# SynchrBuckConverter.net
KiCad netlist of a schematic drawn in Altium Designer
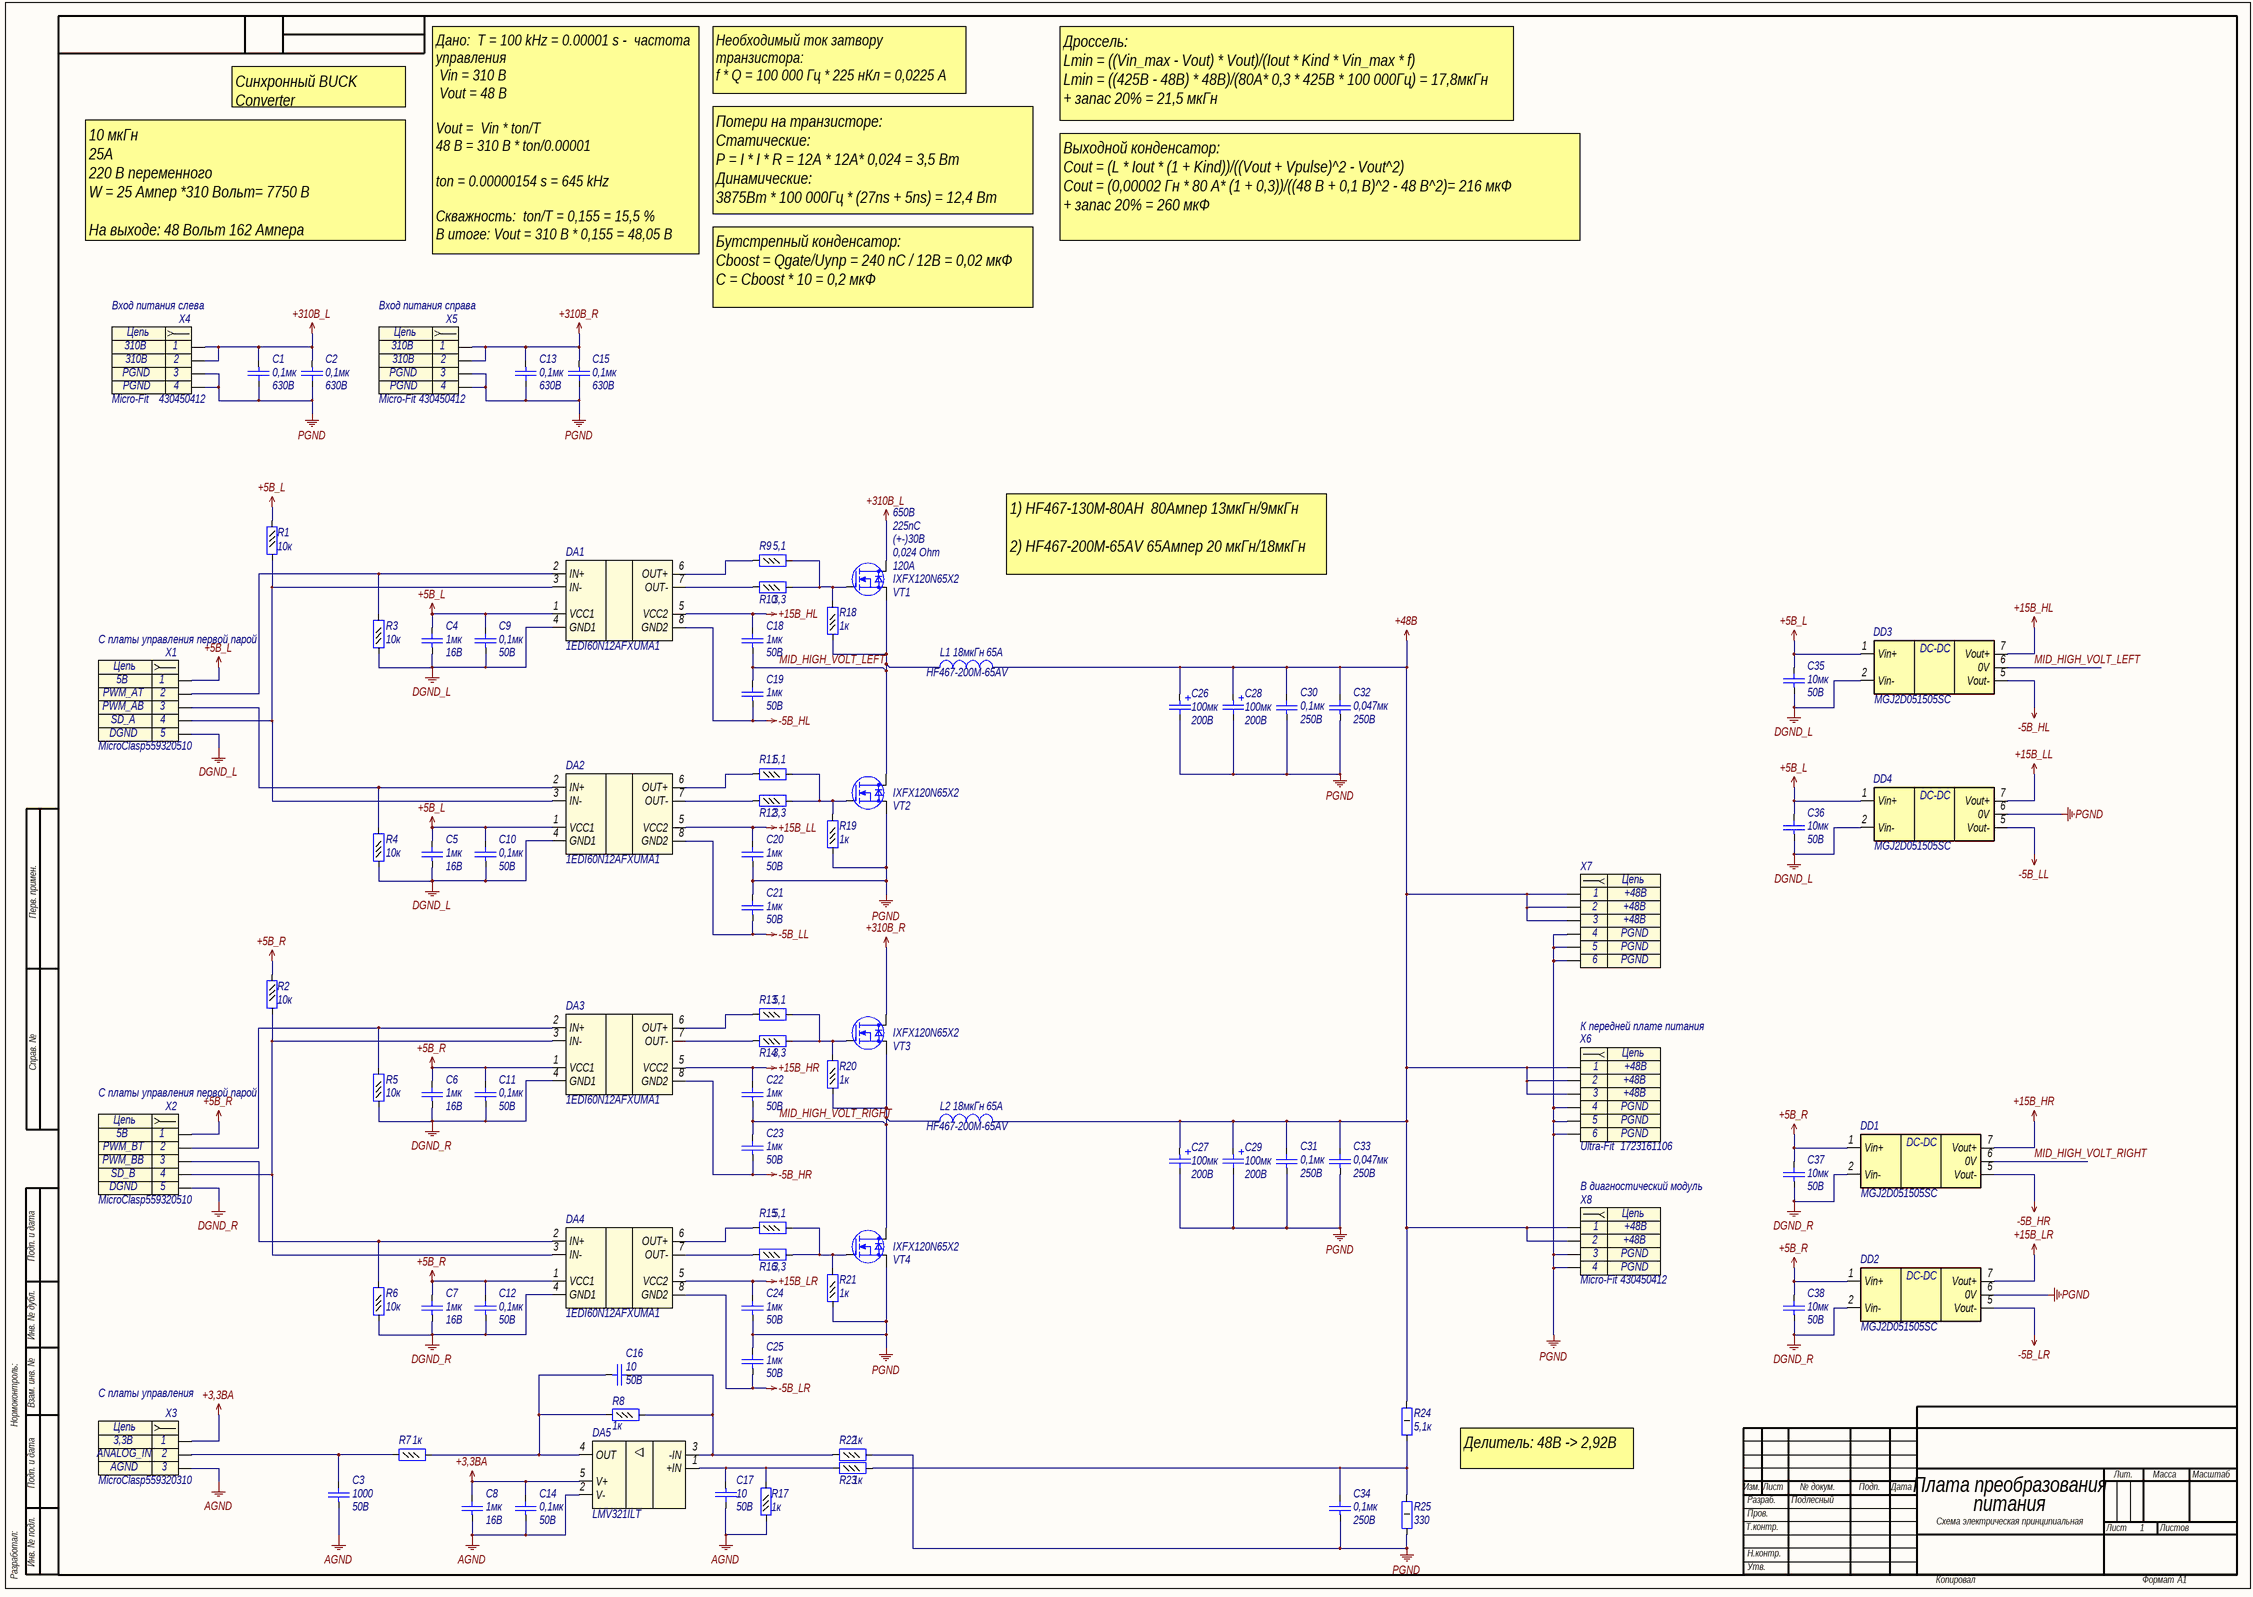
[diagram p0: SynchrBuckConverter.SchDoc]

(export (version "E")
  (design (tool "Eeschema 10.0.6"))
  (components
    (comp (ref "C1")
      (value "0,1мк")
      (footprint "C1812")
      (description "Конденсатор")
      (fields (field (name "VOLTAGE") "630В") (field (name "PART NUMBER") "GRM43DR72J104KW01L"))
      (libsource (lib "MOP44") (part "Capacitor"))
    )
    (comp (ref "C2")
      (value "0,1мк")
      (footprint "C1812")
      (description "Конденсатор")
      (fields (field (name "VOLTAGE") "630В") (field (name "PART NUMBER") "GRM43DR72J104KW01L"))
      (libsource (lib "MOP44") (part "Capacitor"))
    )
    (comp (ref "C3")
      (value "1000")
      (footprint "C0402")
      (description "Конденсатор")
      (fields
        (field (name "VOLTAGE") "50B")
        (field (name "PART NUMBER") "GRM1555C1H102J")
        (field (name "Comment") "Capacitor")
      )
      (libsource (lib "MOP44") (part "Capacitor"))
    )
    (comp (ref "C4")
      (value "1мк")
      (footprint "C0603")
      (description "Конденсатор")
      (fields (field (name "VOLTAGE") "16B") (field (name "PART NUMBER") "GRM188R71C105KA12D**"))
      (libsource (lib "MOP44") (part "Capacitor"))
    )
    (comp (ref "C5")
      (value "1мк")
      (footprint "C0603")
      (description "Конденсатор")
      (fields (field (name "VOLTAGE") "16B") (field (name "PART NUMBER") "GRM188R71C105KA12D**"))
      (libsource (lib "MOP44") (part "Capacitor"))
    )
    (comp (ref "C6")
      (value "1мк")
      (footprint "C0603")
      (description "Конденсатор")
      (fields (field (name "VOLTAGE") "16B") (field (name "PART NUMBER") "GRM188R71C105KA12D**"))
      (libsource (lib "MOP44") (part "Capacitor"))
    )
    (comp (ref "C7")
      (value "1мк")
      (footprint "C0603")
      (description "Конденсатор")
      (fields (field (name "VOLTAGE") "16B") (field (name "PART NUMBER") "GRM188R71C105KA12D**"))
      (libsource (lib "MOP44") (part "Capacitor"))
    )
    (comp (ref "C8")
      (value "1мк")
      (footprint "C0603")
      (description "Конденсатор")
      (fields (field (name "VOLTAGE") "16B") (field (name "PART NUMBER") "GRM188R71C105KA12D**"))
      (libsource (lib "MOP44") (part "Capacitor"))
    )
    (comp (ref "C9")
      (value "0,1мк")
      (footprint "C0402")
      (description "Конденсатор")
      (fields (field (name "VOLTAGE") "50В") (field (name "PART NUMBER") "GRM155R71H104KE14D"))
      (libsource (lib "MOP44") (part "Capacitor"))
    )
    (comp (ref "C10")
      (value "0,1мк")
      (footprint "C0402")
      (description "Конденсатор")
      (fields (field (name "VOLTAGE") "50В") (field (name "PART NUMBER") "GRM155R71H104KE14D"))
      (libsource (lib "MOP44") (part "Capacitor"))
    )
    (comp (ref "C11")
      (value "0,1мк")
      (footprint "C0402")
      (description "Конденсатор")
      (fields (field (name "VOLTAGE") "50В") (field (name "PART NUMBER") "GRM155R71H104KE14D"))
      (libsource (lib "MOP44") (part "Capacitor"))
    )
    (comp (ref "C12")
      (value "0,1мк")
      (footprint "C0402")
      (description "Конденсатор")
      (fields (field (name "VOLTAGE") "50В") (field (name "PART NUMBER") "GRM155R71H104KE14D"))
      (libsource (lib "MOP44") (part "Capacitor"))
    )
    (comp (ref "C13")
      (value "0,1мк")
      (footprint "C1812")
      (description "Конденсатор")
      (fields (field (name "VOLTAGE") "630В") (field (name "PART NUMBER") "GRM43DR72J104KW01L"))
      (libsource (lib "MOP44") (part "Capacitor"))
    )
    (comp (ref "C14")
      (value "0,1мк")
      (footprint "C0402")
      (description "Конденсатор")
      (fields
        (field (name "VOLTAGE") "50В")
        (field (name "PART NUMBER") "GRM155R71H104KE14D")
        (field (name "Comment") "Capacitor")
      )
      (libsource (lib "MOP44") (part "Capacitor"))
    )
    (comp (ref "C15")
      (value "0,1мк")
      (footprint "C1812")
      (description "Конденсатор")
      (fields (field (name "VOLTAGE") "630В") (field (name "PART NUMBER") "GRM43DR72J104KW01L"))
      (libsource (lib "MOP44") (part "Capacitor"))
    )
    (comp (ref "C16")
      (value "10")
      (footprint "C0402")
      (description "Конденсатор")
      (fields
        (field (name "VOLTAGE") "50B")
        (field (name "PART NUMBER") "GRM1535C1H100J")
        (field (name "Comment") "Capacitor")
      )
      (libsource (lib "MOP44") (part "Capacitor"))
    )
    (comp (ref "C17")
      (value "10")
      (footprint "C0402")
      (description "Конденсатор")
      (fields
        (field (name "VOLTAGE") "50B")
        (field (name "PART NUMBER") "GRM1535C1H100J")
        (field (name "Comment") "Capacitor")
      )
      (libsource (lib "MOP44") (part "Capacitor"))
    )
    (comp (ref "C18")
      (value "1мк")
      (footprint "C0805")
      (description "Конденсатор")
      (fields (field (name "VOLTAGE") "50B") (field (name "PART NUMBER") "GRM21BR71H105K"))
      (libsource (lib "MOP44") (part "Capacitor"))
    )
    (comp (ref "C19")
      (value "1мк")
      (footprint "C0805")
      (description "Конденсатор")
      (fields (field (name "VOLTAGE") "50B") (field (name "PART NUMBER") "GRM21BR71H105K"))
      (libsource (lib "MOP44") (part "Capacitor"))
    )
    (comp (ref "C20")
      (value "1мк")
      (footprint "C0805")
      (description "Конденсатор")
      (fields (field (name "VOLTAGE") "50B") (field (name "PART NUMBER") "GRM21BR71H105K"))
      (libsource (lib "MOP44") (part "Capacitor"))
    )
    (comp (ref "C21")
      (value "1мк")
      (footprint "C0805")
      (description "Конденсатор")
      (fields (field (name "VOLTAGE") "50B") (field (name "PART NUMBER") "GRM21BR71H105K"))
      (libsource (lib "MOP44") (part "Capacitor"))
    )
    (comp (ref "C22")
      (value "1мк")
      (footprint "C0805")
      (description "Конденсатор")
      (fields (field (name "VOLTAGE") "50B") (field (name "PART NUMBER") "GRM21BR71H105K"))
      (libsource (lib "MOP44") (part "Capacitor"))
    )
    (comp (ref "C23")
      (value "1мк")
      (footprint "C0805")
      (description "Конденсатор")
      (fields (field (name "VOLTAGE") "50B") (field (name "PART NUMBER") "GRM21BR71H105K"))
      (libsource (lib "MOP44") (part "Capacitor"))
    )
    (comp (ref "C24")
      (value "1мк")
      (footprint "C0805")
      (description "Конденсатор")
      (fields (field (name "VOLTAGE") "50B") (field (name "PART NUMBER") "GRM21BR71H105K"))
      (libsource (lib "MOP44") (part "Capacitor"))
    )
    (comp (ref "C25")
      (value "1мк")
      (footprint "C0805")
      (description "Конденсатор")
      (fields (field (name "VOLTAGE") "50B") (field (name "PART NUMBER") "GRM21BR71H105K"))
      (libsource (lib "MOP44") (part "Capacitor"))
    )
    (comp (ref "C26")
      (value "100мк")
      (footprint "Cap_SMD_radial_polar(18x21.5)")
      (description "Конденсатор полярный")
      (fields
        (field (name "VOLTAGE") "200В")
        (field (name "PART NUMBER") "EEV-EB2D101M")
        (field (name "Comment") "Capacitor_pol")
      )
      (libsource (lib "MOP44") (part "Capacitor_pol"))
    )
    (comp (ref "C27")
      (value "100мк")
      (footprint "Cap_SMD_radial_polar(18x21.5)")
      (description "Конденсатор полярный")
      (fields
        (field (name "VOLTAGE") "200В")
        (field (name "PART NUMBER") "EEV-EB2D101M")
        (field (name "Comment") "Capacitor_pol")
      )
      (libsource (lib "MOP44") (part "Capacitor_pol"))
    )
    (comp (ref "C28")
      (value "100мк")
      (footprint "Cap_SMD_radial_polar(18x21.5)")
      (description "Конденсатор полярный")
      (fields
        (field (name "VOLTAGE") "200В")
        (field (name "PART NUMBER") "EEV-EB2D101M")
        (field (name "Comment") "Capacitor_pol")
      )
      (libsource (lib "MOP44") (part "Capacitor_pol"))
    )
    (comp (ref "C29")
      (value "100мк")
      (footprint "Cap_SMD_radial_polar(18x21.5)")
      (description "Конденсатор полярный")
      (fields
        (field (name "VOLTAGE") "200В")
        (field (name "PART NUMBER") "EEV-EB2D101M")
        (field (name "Comment") "Capacitor_pol")
      )
      (libsource (lib "MOP44") (part "Capacitor_pol"))
    )
    (comp (ref "C30")
      (value "0,1мк")
      (footprint "C1206")
      (description "Конденсатор")
      (fields (field (name "VOLTAGE") "250В") (field (name "PART NUMBER") "GRM31CR72E104K"))
      (libsource (lib "MOP44") (part "Capacitor"))
    )
    (comp (ref "C31")
      (value "0,1мк")
      (footprint "C1206")
      (description "Конденсатор")
      (fields (field (name "VOLTAGE") "250В") (field (name "PART NUMBER") "GRM31CR72E104K"))
      (libsource (lib "MOP44") (part "Capacitor"))
    )
    (comp (ref "C32")
      (value "0,047мк")
      (footprint "C1206")
      (description "Конденсатор")
      (fields (field (name "VOLTAGE") "250В") (field (name "PART NUMBER") "GRM31CR72E473K"))
      (libsource (lib "MOP44") (part "Capacitor"))
    )
    (comp (ref "C33")
      (value "0,047мк")
      (footprint "C1206")
      (description "Конденсатор")
      (fields (field (name "VOLTAGE") "250В") (field (name "PART NUMBER") "GRM31CR72E473K"))
      (libsource (lib "MOP44") (part "Capacitor"))
    )
    (comp (ref "C34")
      (value "0,1мк")
      (footprint "C1206")
      (description "Конденсатор")
      (fields (field (name "VOLTAGE") "250В") (field (name "PART NUMBER") "GRM31CR72E104K"))
      (libsource (lib "MOP44") (part "Capacitor"))
    )
    (comp (ref "C35")
      (value "10мк")
      (footprint "C1210")
      (description "Конденсатор")
      (fields (field (name "VOLTAGE") "50В") (field (name "PART NUMBER") "C3225X7R1H106K250AC"))
      (libsource (lib "MOP44") (part "Capacitor"))
    )
    (comp (ref "C36")
      (value "10мк")
      (footprint "C1210")
      (description "Конденсатор")
      (fields (field (name "VOLTAGE") "50В") (field (name "PART NUMBER") "C3225X7R1H106K250AC"))
      (libsource (lib "MOP44") (part "Capacitor"))
    )
    (comp (ref "C37")
      (value "10мк")
      (footprint "C1210")
      (description "Конденсатор")
      (fields (field (name "VOLTAGE") "50В") (field (name "PART NUMBER") "C3225X7R1H106K250AC"))
      (libsource (lib "MOP44") (part "Capacitor"))
    )
    (comp (ref "C38")
      (value "10мк")
      (footprint "C1210")
      (description "Конденсатор")
      (fields (field (name "VOLTAGE") "50В") (field (name "PART NUMBER") "C3225X7R1H106K250AC"))
      (libsource (lib "MOP44") (part "Capacitor"))
    )
    (comp (ref "DA1")
      (value "1EDI60N12AF")
      (footprint "PG-DSO-8")
      (description "Single Channel MOSFET Gate Driver IC")
      (fields (field (name "PART NUMBER") "1EDI60N12AFXUMA1"))
      (libsource (lib "MOP44") (part "1EDI60N12AF"))
    )
    (comp (ref "DA2")
      (value "1EDI60N12AF")
      (footprint "PG-DSO-8")
      (description "Single Channel MOSFET Gate Driver IC")
      (fields (field (name "PART NUMBER") "1EDI60N12AFXUMA1"))
      (libsource (lib "MOP44") (part "1EDI60N12AF"))
    )
    (comp (ref "DA3")
      (value "1EDI60N12AF")
      (footprint "PG-DSO-8")
      (description "Single Channel MOSFET Gate Driver IC")
      (fields (field (name "PART NUMBER") "1EDI60N12AFXUMA1"))
      (libsource (lib "MOP44") (part "1EDI60N12AF"))
    )
    (comp (ref "DA4")
      (value "1EDI60N12AF")
      (footprint "PG-DSO-8")
      (description "Single Channel MOSFET Gate Driver IC")
      (fields (field (name "PART NUMBER") "1EDI60N12AFXUMA1"))
      (libsource (lib "MOP44") (part "1EDI60N12AF"))
    )
    (comp (ref "DA5")
      (value "LMV321ILT")
      (footprint "SOT23-5")
      (description "HIGH-DRIVE OPERATIONAL AMPLIFIERS WITH SHUTDOWN")
      (libsource (lib "MOP44") (part "LMV321ILT"))
    )
    (comp (ref "DD1")
      (value "MGJ2DXX XXXX S C-RXX")
      (footprint "SIP7")
      (description "DC/DC преобразователь")
      (fields
        (field (name "PART NUMBER") "MGJ2D051505SC")
        (field (name "MANUFACTURER") "Murata Power Solutions")
      )
      (libsource (lib "MOP44") (part "MGJ2DXX XXXX S C-RXX"))
    )
    (comp (ref "DD2")
      (value "MGJ2DXX XXXX S C-RXX")
      (footprint "SIP7")
      (description "DC/DC преобразователь")
      (fields
        (field (name "PART NUMBER") "MGJ2D051505SC")
        (field (name "MANUFACTURER") "Murata Power Solutions")
      )
      (libsource (lib "MOP44") (part "MGJ2DXX XXXX S C-RXX"))
    )
    (comp (ref "DD3")
      (value "MGJ2DXX XXXX S C-RXX")
      (footprint "SIP7")
      (description "DC/DC преобразователь")
      (fields
        (field (name "PART NUMBER") "MGJ2D051505SC")
        (field (name "MANUFACTURER") "Murata Power Solutions")
      )
      (libsource (lib "MOP44") (part "MGJ2DXX XXXX S C-RXX"))
    )
    (comp (ref "DD4")
      (value "MGJ2DXX XXXX S C-RXX")
      (footprint "SIP7")
      (description "DC/DC преобразователь")
      (fields
        (field (name "PART NUMBER") "MGJ2D051505SC")
        (field (name "MANUFACTURER") "Murata Power Solutions")
      )
      (libsource (lib "MOP44") (part "MGJ2DXX XXXX S C-RXX"))
    )
    (comp (ref "L1")
      (value "18мкГн")
      (footprint "HF467-200M-65AV")
      (description "EMI Suppression Filter")
      (fields
        (field (name "RATED CURRENT") "65A")
        (field (name "PART NUMBER") "HF467-200M-65AV")
        (field (name "Comment") "Inductor")
      )
      (libsource (lib "MOP44") (part "Inductor"))
    )
    (comp (ref "L2")
      (value "18мкГн")
      (footprint "HF467-200M-65AV")
      (description "EMI Suppression Filter")
      (fields
        (field (name "RATED CURRENT") "65A")
        (field (name "PART NUMBER") "HF467-200M-65AV")
        (field (name "Comment") "Inductor")
      )
      (libsource (lib "MOP44") (part "Inductor"))
    )
    (comp (ref "R1")
      (value "10к")
      (footprint "R0402")
      (description "Резистор")
      (fields (field (name "PART NUMBER") "RC0402FR-0710KL") (field (name "POWER") "0,062Вт"))
      (libsource (lib "") (part "Resistor_0,062Вт_2"))
    )
    (comp (ref "R2")
      (value "10к")
      (footprint "R0402")
      (description "Резистор")
      (fields (field (name "PART NUMBER") "RC0402FR-0710KL") (field (name "POWER") "0,062Вт"))
      (libsource (lib "") (part "Resistor_0,062Вт_2"))
    )
    (comp (ref "R3")
      (value "10к")
      (footprint "R0402")
      (description "Резистор")
      (fields (field (name "PART NUMBER") "RC0402FR-0710KL") (field (name "POWER") "0,062Вт"))
      (libsource (lib "") (part "Resistor_0,062Вт_1"))
    )
    (comp (ref "R4")
      (value "10к")
      (footprint "R0402")
      (description "Резистор")
      (fields (field (name "PART NUMBER") "RC0402FR-0710KL") (field (name "POWER") "0,062Вт"))
      (libsource (lib "") (part "Resistor_0,062Вт_1"))
    )
    (comp (ref "R5")
      (value "10к")
      (footprint "R0402")
      (description "Резистор")
      (fields (field (name "PART NUMBER") "RC0402FR-0710KL") (field (name "POWER") "0,062Вт"))
      (libsource (lib "") (part "Resistor_0,062Вт_1"))
    )
    (comp (ref "R6")
      (value "10к")
      (footprint "R0402")
      (description "Резистор")
      (fields (field (name "PART NUMBER") "RC0402FR-0710KL") (field (name "POWER") "0,062Вт"))
      (libsource (lib "") (part "Resistor_0,062Вт_1"))
    )
    (comp (ref "R7")
      (value "1к")
      (footprint "R0402")
      (description "Резистор")
      (fields (field (name "PART NUMBER") "RC0402FR-071KL") (field (name "POWER") "0,062Вт"))
      (libsource (lib "MOP44") (part "Resistor_0,062Вт"))
    )
    (comp (ref "R8")
      (value "1к")
      (footprint "R0402")
      (description "Резистор")
      (fields (field (name "PART NUMBER") "RC0402FR-071KL") (field (name "POWER") "0,062Вт"))
      (libsource (lib "MOP44") (part "Resistor_0,062Вт"))
    )
    (comp (ref "R9")
      (value "5,1")
      (footprint "R0603")
      (description "Резистор")
      (fields (field (name "PART NUMBER") "RC0603FR-075R1L") (field (name "POWER") "0,062Вт"))
      (libsource (lib "MOP44") (part "Resistor_0,062Вт"))
    )
    (comp (ref "R10")
      (value "3,3")
      (footprint "R0603")
      (description "Резистор")
      (fields (field (name "PART NUMBER") "RC0603FR-073R3L") (field (name "POWER") "0,062Вт"))
      (libsource (lib "MOP44") (part "Resistor_0,062Вт"))
    )
    (comp (ref "R11")
      (value "5,1")
      (footprint "R0603")
      (description "Резистор")
      (fields (field (name "PART NUMBER") "RC0603FR-075R1L") (field (name "POWER") "0,062Вт"))
      (libsource (lib "MOP44") (part "Resistor_0,062Вт"))
    )
    (comp (ref "R12")
      (value "3,3")
      (footprint "R0603")
      (description "Резистор")
      (fields (field (name "PART NUMBER") "RC0603FR-073R3L") (field (name "POWER") "0,062Вт"))
      (libsource (lib "MOP44") (part "Resistor_0,062Вт"))
    )
    (comp (ref "R13")
      (value "5,1")
      (footprint "R0603")
      (description "Резистор")
      (fields (field (name "PART NUMBER") "RC0603FR-075R1L") (field (name "POWER") "0,062Вт"))
      (libsource (lib "MOP44") (part "Resistor_0,062Вт"))
    )
    (comp (ref "R14")
      (value "3,3")
      (footprint "R0603")
      (description "Резистор")
      (fields (field (name "PART NUMBER") "RC0603FR-073R3L") (field (name "POWER") "0,062Вт"))
      (libsource (lib "MOP44") (part "Resistor_0,062Вт"))
    )
    (comp (ref "R15")
      (value "5,1")
      (footprint "R0603")
      (description "Резистор")
      (fields (field (name "PART NUMBER") "RC0603FR-075R1L") (field (name "POWER") "0,062Вт"))
      (libsource (lib "MOP44") (part "Resistor_0,062Вт"))
    )
    (comp (ref "R16")
      (value "3,3")
      (footprint "R0603")
      (description "Резистор")
      (fields (field (name "PART NUMBER") "RC0603FR-073R3L") (field (name "POWER") "0,062Вт"))
      (libsource (lib "MOP44") (part "Resistor_0,062Вт"))
    )
    (comp (ref "R17")
      (value "1к")
      (footprint "R0402")
      (description "Резистор")
      (fields (field (name "PART NUMBER") "RC0402FR-071KL") (field (name "POWER") "0,062Вт"))
      (libsource (lib "") (part "Resistor_0,062Вт_1"))
    )
    (comp (ref "R18")
      (value "1к")
      (footprint "R0603")
      (description "Резистор")
      (fields (field (name "PART NUMBER") "RC0603FR-071KL") (field (name "POWER") "0,062Вт"))
      (libsource (lib "") (part "Resistor_0,062Вт_1"))
    )
    (comp (ref "R19")
      (value "1к")
      (footprint "R0603")
      (description "Резистор")
      (fields (field (name "PART NUMBER") "RC0603FR-071KL") (field (name "POWER") "0,062Вт"))
      (libsource (lib "") (part "Resistor_0,062Вт_1"))
    )
    (comp (ref "R20")
      (value "1к")
      (footprint "R0603")
      (description "Резистор")
      (fields (field (name "PART NUMBER") "RC0603FR-071KL") (field (name "POWER") "0,062Вт"))
      (libsource (lib "") (part "Resistor_0,062Вт_1"))
    )
    (comp (ref "R21")
      (value "1к")
      (footprint "R0603")
      (description "Резистор")
      (fields (field (name "PART NUMBER") "RC0603FR-071KL") (field (name "POWER") "0,062Вт"))
      (libsource (lib "") (part "Resistor_0,062Вт_1"))
    )
    (comp (ref "R22")
      (value "1к")
      (footprint "R0402")
      (description "Резистор")
      (fields (field (name "PART NUMBER") "RC0402FR-071KL") (field (name "POWER") "0,062Вт"))
      (libsource (lib "MOP44") (part "Resistor_0,062Вт"))
    )
    (comp (ref "R23")
      (value "1к")
      (footprint "R0402")
      (description "Резистор")
      (fields (field (name "PART NUMBER") "RC0402FR-071KL") (field (name "POWER") "0,062Вт"))
      (libsource (lib "MOP44") (part "Resistor_0,062Вт"))
    )
    (comp (ref "R24")
      (value "5,1к")
      (footprint "R2512")
      (description "Резистор")
      (fields (field (name "PART NUMBER") "RC2512FR-075K1") (field (name "POWER") "1Вт"))
      (libsource (lib "MOP44") (part "Resistor_1Вт"))
    )
    (comp (ref "R25")
      (value "330")
      (footprint "R2512")
      (description "Резистор")
      (fields (field (name "PART NUMBER") "RC2512FR-07330RL") (field (name "POWER") "1Вт"))
      (libsource (lib "MOP44") (part "Resistor_1Вт"))
    )
    (comp (ref "VT1")
      (value "N-MOSFET")
      (footprint "TO-247_V")
      (fields
        (field (name "V DRAIN-SOURCE MAX") "650B")
        (field (name "RDS") "0,024 Ohm")
        (field (name "GATE-TO-SOURCE VOLTAGE") "(+-)30B")
        (field (name "CONTINUOUS DRAIN CURRENT") "120A")
        (field (name "TOTAL GATE CHARGE") "225nC")
        (field (name "PART NUMBER") "IXFX120N65X2")
        (field (name "MANUFACTURER") "IXYS")
      )
      (libsource (lib "MOP44") (part "N-MOSFET"))
    )
    (comp (ref "VT2")
      (value "N-MOSFET")
      (footprint "TO-247_V")
      (fields (field (name "PART NUMBER") "IXFX120N65X2") (field (name "MANUFACTURER") "IXYS"))
      (libsource (lib "MOP44") (part "N-MOSFET"))
    )
    (comp (ref "VT3")
      (value "N-MOSFET")
      (footprint "TO-247_V")
      (fields (field (name "PART NUMBER") "IXFX120N65X2") (field (name "MANUFACTURER") "IXYS"))
      (libsource (lib "MOP44") (part "N-MOSFET"))
    )
    (comp (ref "VT4")
      (value "N-MOSFET")
      (footprint "TO-247_V")
      (fields (field (name "PART NUMBER") "IXFX120N65X2") (field (name "MANUFACTURER") "IXYS"))
      (libsource (lib "MOP44") (part "N-MOSFET"))
    )
    (comp (ref "X1")
      (value "C платы управления первой парой")
      (footprint "MOLEX_559320510")
      (description "Разъем - 5 конт. розетка")
      (fields (field (name "PART NAME") "MicroClasp") (field (name "PART NUMBER") "559320510"))
      (libsource (lib "MOP44") (part "Header_5_sct"))
    )
    (comp (ref "X2")
      (value "C платы управления первой парой")
      (footprint "MOLEX_559320510")
      (description "Разъем - 5 конт. розетка")
      (fields (field (name "PART NAME") "MicroClasp") (field (name "PART NUMBER") "559320510"))
      (libsource (lib "MOP44") (part "Header_5_sct"))
    )
    (comp (ref "X3")
      (value "C платы управления")
      (footprint "MOLEX_559320310")
      (description "Разъем - 3 конт. розетка")
      (fields (field (name "PART NAME") "MicroClasp") (field (name "PART NUMBER") "559320310"))
      (libsource (lib "MOP44") (part "Header_3_sct"))
    )
    (comp (ref "X4")
      (value "Вход питания слева")
      (footprint "MOLEX_430450412")
      (description "Разъем - 4 конт. розетка")
      (fields (field (name "PART NAME") "Micro-Fit") (field (name "PART NUMBER") "430450412"))
      (libsource (lib "MOP44") (part "Header_4_sct"))
    )
    (comp (ref "X5")
      (value "Вход питания справа")
      (footprint "MOLEX_430450412")
      (description "Разъем - 4 конт. розетка")
      (fields (field (name "PART NAME") "Micro-Fit") (field (name "PART NUMBER") "430450412"))
      (libsource (lib "MOP44") (part "Header_4_sct"))
    )
    (comp (ref "X6")
      (value "К передней плате питания")
      (footprint "MOLEX_1723161106")
      (description "Разъем - 6 конт. розетка")
      (fields (field (name "PART NAME") "Ultra-Fit") (field (name "PART NUMBER") "1723161106"))
      (libsource (lib "MOP44") (part "Header_6_sct"))
    )
    (comp (ref "X7")
      (value "Header_6_sct")
      (footprint "MOLEX_1722981106_HOLE")
      (description "Разъем - 6 конт. розетка")
      (fields (field (name "PART NUMBER") "1722981106"))
      (libsource (lib "MOP44") (part "Header_6_sct"))
    )
    (comp (ref "X8")
      (value "В диагностический модуль")
      (footprint "MOLEX_430450412")
      (description "Разъем - 4 конт. розетка")
      (fields (field (name "PART NAME") "Micro-Fit") (field (name "PART NUMBER") "430450412"))
      (libsource (lib "") (part "Header_4_sct_1"))
    )
  )
  (nets
    (net (code "1") (name "+3,3BA") (class "Default")
      (node (ref "C14") (pin "2") (pinfunction "2_2") (pintype "passive"))
      (node (ref "C8") (pin "2") (pinfunction "2_2") (pintype "passive"))
      (node (ref "DA5") (pin "5") (pinfunction "V+_5") (pintype "passive"))
      (node (ref "X3") (pin "1") (pinfunction "1_1") (pintype "passive"))
    )
    (net (code "2") (name "+5B_L") (class "Default")
      (node (ref "C10") (pin "2") (pinfunction "2_2") (pintype "passive"))
      (node (ref "C35") (pin "2") (pinfunction "2_2") (pintype "passive"))
      (node (ref "C36") (pin "2") (pinfunction "2_2") (pintype "passive"))
      (node (ref "C4") (pin "2") (pinfunction "2_2") (pintype "passive"))
      (node (ref "C5") (pin "2") (pinfunction "2_2") (pintype "passive"))
      (node (ref "C9") (pin "2") (pinfunction "2_2") (pintype "passive"))
      (node (ref "DA1") (pin "1") (pinfunction "VCC1_1") (pintype "passive"))
      (node (ref "DA2") (pin "1") (pinfunction "VCC1_1") (pintype "passive"))
      (node (ref "DD3") (pin "1") (pinfunction "Vin+_1") (pintype "passive"))
      (node (ref "DD4") (pin "1") (pinfunction "Vin+_1") (pintype "passive"))
      (node (ref "R1") (pin "1") (pinfunction "1_1") (pintype "passive"))
      (node (ref "X1") (pin "1") (pinfunction "1_1") (pintype "passive"))
    )
    (net (code "3") (name "+5B_R") (class "Default")
      (node (ref "C11") (pin "2") (pinfunction "2_2") (pintype "passive"))
      (node (ref "C12") (pin "2") (pinfunction "2_2") (pintype "passive"))
      (node (ref "C37") (pin "2") (pinfunction "2_2") (pintype "passive"))
      (node (ref "C38") (pin "2") (pinfunction "2_2") (pintype "passive"))
      (node (ref "C6") (pin "2") (pinfunction "2_2") (pintype "passive"))
      (node (ref "C7") (pin "2") (pinfunction "2_2") (pintype "passive"))
      (node (ref "DA3") (pin "1") (pinfunction "VCC1_1") (pintype "passive"))
      (node (ref "DA4") (pin "1") (pinfunction "VCC1_1") (pintype "passive"))
      (node (ref "DD1") (pin "1") (pinfunction "Vin+_1") (pintype "passive"))
      (node (ref "DD2") (pin "1") (pinfunction "Vin+_1") (pintype "passive"))
      (node (ref "R2") (pin "1") (pinfunction "1_1") (pintype "passive"))
      (node (ref "X2") (pin "1") (pinfunction "1_1") (pintype "passive"))
    )
    (net (code "4") (name "+15B_HR") (class "Default")
      (node (ref "C22") (pin "2") (pinfunction "2_2") (pintype "passive"))
      (node (ref "DA3") (pin "5") (pinfunction "VCC2_5") (pintype "passive"))
      (node (ref "DD1") (pin "7") (pinfunction "Vout+_7") (pintype "passive"))
    )
    (net (code "5") (name "+15B_LL") (class "Default")
      (node (ref "C20") (pin "2") (pinfunction "2_2") (pintype "passive"))
      (node (ref "DA2") (pin "5") (pinfunction "VCC2_5") (pintype "passive"))
      (node (ref "DD4") (pin "7") (pinfunction "Vout+_7") (pintype "passive"))
    )
    (net (code "6") (name "+15B_LR") (class "Default")
      (node (ref "C24") (pin "2") (pinfunction "2_2") (pintype "passive"))
      (node (ref "DA4") (pin "5") (pinfunction "VCC2_5") (pintype "passive"))
      (node (ref "DD2") (pin "7") (pinfunction "Vout+_7") (pintype "passive"))
    )
    (net (code "7") (name "+15B_НL") (class "Default")
      (node (ref "C18") (pin "2") (pinfunction "2_2") (pintype "passive"))
      (node (ref "DA1") (pin "5") (pinfunction "VCC2_5") (pintype "passive"))
      (node (ref "DD3") (pin "7") (pinfunction "Vout+_7") (pintype "passive"))
    )
    (net (code "8") (name "+48B") (class "Default")
      (node (ref "C26") (pin "1") (pinfunction "1_1") (pintype "passive"))
      (node (ref "C27") (pin "1") (pinfunction "1_1") (pintype "passive"))
      (node (ref "C28") (pin "1") (pinfunction "1_1") (pintype "passive"))
      (node (ref "C29") (pin "1") (pinfunction "1_1") (pintype "passive"))
      (node (ref "C30") (pin "2") (pinfunction "2_2") (pintype "passive"))
      (node (ref "C31") (pin "2") (pinfunction "2_2") (pintype "passive"))
      (node (ref "C32") (pin "2") (pinfunction "2_2") (pintype "passive"))
      (node (ref "C33") (pin "2") (pinfunction "2_2") (pintype "passive"))
      (node (ref "L1") (pin "2") (pinfunction "2_2") (pintype "passive"))
      (node (ref "L2") (pin "2") (pinfunction "2_2") (pintype "passive"))
      (node (ref "R24") (pin "2") (pinfunction "5_2") (pintype "passive"))
      (node (ref "X6") (pin "1") (pinfunction "1_1") (pintype "passive"))
      (node (ref "X6") (pin "2") (pinfunction "2_2") (pintype "passive"))
      (node (ref "X6") (pin "3") (pinfunction "3_3") (pintype "passive"))
      (node (ref "X7") (pin "1") (pinfunction "1_1") (pintype "passive"))
      (node (ref "X7") (pin "2") (pinfunction "2_2") (pintype "passive"))
      (node (ref "X7") (pin "3") (pinfunction "3_3") (pintype "passive"))
      (node (ref "X8") (pin "1") (pinfunction "1_1") (pintype "passive"))
      (node (ref "X8") (pin "2") (pinfunction "2_2") (pintype "passive"))
    )
    (net (code "9") (name "+310B_L") (class "Default")
      (node (ref "C1") (pin "1") (pinfunction "1_1") (pintype "passive"))
      (node (ref "C2") (pin "1") (pinfunction "1_1") (pintype "passive"))
      (node (ref "VT1") (pin "2") (pinfunction "D_2") (pintype "passive"))
      (node (ref "X4") (pin "1") (pinfunction "1_1") (pintype "passive"))
      (node (ref "X4") (pin "2") (pinfunction "2_2") (pintype "passive"))
    )
    (net (code "10") (name "+310B_R") (class "Default")
      (node (ref "C13") (pin "1") (pinfunction "1_1") (pintype "passive"))
      (node (ref "C15") (pin "1") (pinfunction "1_1") (pintype "passive"))
      (node (ref "VT3") (pin "2") (pinfunction "D_2") (pintype "passive"))
      (node (ref "X5") (pin "1") (pinfunction "1_1") (pintype "passive"))
      (node (ref "X5") (pin "2") (pinfunction "2_2") (pintype "passive"))
    )
    (net (code "11") (name "-5B_HL") (class "Default")
      (node (ref "C19") (pin "1") (pinfunction "1_1") (pintype "passive"))
      (node (ref "DA1") (pin "8") (pinfunction "GND2_8") (pintype "passive"))
      (node (ref "DD3") (pin "5") (pinfunction "Vout-_5") (pintype "passive"))
    )
    (net (code "12") (name "-5B_HR") (class "Default")
      (node (ref "C23") (pin "1") (pinfunction "1_1") (pintype "passive"))
      (node (ref "DA3") (pin "8") (pinfunction "GND2_8") (pintype "passive"))
      (node (ref "DD1") (pin "5") (pinfunction "Vout-_5") (pintype "passive"))
    )
    (net (code "13") (name "-5B_LL") (class "Default")
      (node (ref "C21") (pin "1") (pinfunction "1_1") (pintype "passive"))
      (node (ref "DA2") (pin "8") (pinfunction "GND2_8") (pintype "passive"))
      (node (ref "DD4") (pin "5") (pinfunction "Vout-_5") (pintype "passive"))
    )
    (net (code "14") (name "-5B_LR") (class "Default")
      (node (ref "C25") (pin "1") (pinfunction "1_1") (pintype "passive"))
      (node (ref "DA4") (pin "8") (pinfunction "GND2_8") (pintype "passive"))
      (node (ref "DD2") (pin "5") (pinfunction "Vout-_5") (pintype "passive"))
    )
    (net (code "15") (name "/MID_HIGH_VOLT_LEFT") (class "Default")
      (node (ref "C18") (pin "1") (pinfunction "1_1") (pintype "passive"))
      (node (ref "C19") (pin "2") (pinfunction "2_2") (pintype "passive"))
      (node (ref "DD3") (pin "6") (pinfunction "0V_6") (pintype "passive"))
      (node (ref "L1") (pin "1") (pinfunction "1_1") (pintype "passive"))
      (node (ref "R18") (pin "1") (pinfunction "1_1") (pintype "passive"))
      (node (ref "VT1") (pin "3") (pinfunction "S_3") (pintype "passive"))
      (node (ref "VT2") (pin "2") (pinfunction "D_2") (pintype "passive"))
    )
    (net (code "16") (name "/MID_HIGH_VOLT_RIGHT") (class "Default")
      (node (ref "C22") (pin "1") (pinfunction "1_1") (pintype "passive"))
      (node (ref "C23") (pin "2") (pinfunction "2_2") (pintype "passive"))
      (node (ref "DD1") (pin "6") (pinfunction "0V_6") (pintype "passive"))
      (node (ref "L2") (pin "1") (pinfunction "1_1") (pintype "passive"))
      (node (ref "R20") (pin "1") (pinfunction "1_1") (pintype "passive"))
      (node (ref "VT3") (pin "3") (pinfunction "S_3") (pintype "passive"))
      (node (ref "VT4") (pin "2") (pinfunction "D_2") (pintype "passive"))
    )
    (net (code "17") (name "AGND") (class "Default")
      (node (ref "C14") (pin "1") (pinfunction "1_1") (pintype "passive"))
      (node (ref "C17") (pin "2") (pinfunction "2_2") (pintype "passive"))
      (node (ref "C3") (pin "1") (pinfunction "1_1") (pintype "passive"))
      (node (ref "C8") (pin "1") (pinfunction "1_1") (pintype "passive"))
      (node (ref "DA5") (pin "2") (pinfunction "V-_2") (pintype "passive"))
      (node (ref "R17") (pin "1") (pinfunction "1_1") (pintype "passive"))
      (node (ref "X3") (pin "3") (pinfunction "3_3") (pintype "passive"))
    )
    (net (code "18") (name "DGND_L") (class "Default")
      (node (ref "C10") (pin "1") (pinfunction "1_1") (pintype "passive"))
      (node (ref "C35") (pin "1") (pinfunction "1_1") (pintype "passive"))
      (node (ref "C36") (pin "1") (pinfunction "1_1") (pintype "passive"))
      (node (ref "C4") (pin "1") (pinfunction "1_1") (pintype "passive"))
      (node (ref "C5") (pin "1") (pinfunction "1_1") (pintype "passive"))
      (node (ref "C9") (pin "1") (pinfunction "1_1") (pintype "passive"))
      (node (ref "DA1") (pin "4") (pinfunction "GND1_4") (pintype "passive"))
      (node (ref "DA2") (pin "4") (pinfunction "GND1_4") (pintype "passive"))
      (node (ref "DD3") (pin "2") (pinfunction "Vin-_2") (pintype "passive"))
      (node (ref "DD4") (pin "2") (pinfunction "Vin-_2") (pintype "passive"))
      (node (ref "R3") (pin "1") (pinfunction "1_1") (pintype "passive"))
      (node (ref "R4") (pin "1") (pinfunction "1_1") (pintype "passive"))
      (node (ref "X1") (pin "5") (pinfunction "5_5") (pintype "passive"))
    )
    (net (code "19") (name "DGND_R") (class "Default")
      (node (ref "C11") (pin "1") (pinfunction "1_1") (pintype "passive"))
      (node (ref "C12") (pin "1") (pinfunction "1_1") (pintype "passive"))
      (node (ref "C37") (pin "1") (pinfunction "1_1") (pintype "passive"))
      (node (ref "C38") (pin "1") (pinfunction "1_1") (pintype "passive"))
      (node (ref "C6") (pin "1") (pinfunction "1_1") (pintype "passive"))
      (node (ref "C7") (pin "1") (pinfunction "1_1") (pintype "passive"))
      (node (ref "DA3") (pin "4") (pinfunction "GND1_4") (pintype "passive"))
      (node (ref "DA4") (pin "4") (pinfunction "GND1_4") (pintype "passive"))
      (node (ref "DD1") (pin "2") (pinfunction "Vin-_2") (pintype "passive"))
      (node (ref "DD2") (pin "2") (pinfunction "Vin-_2") (pintype "passive"))
      (node (ref "R5") (pin "1") (pinfunction "1_1") (pintype "passive"))
      (node (ref "R6") (pin "1") (pinfunction "1_1") (pintype "passive"))
      (node (ref "X2") (pin "5") (pinfunction "5_5") (pintype "passive"))
    )
    (net (code "20") (name "Net-(C3-Pad2)") (class "Default")
      (node (ref "C3") (pin "2") (pinfunction "2_2") (pintype "passive"))
      (node (ref "R7") (pin "1") (pinfunction "1_1") (pintype "passive"))
      (node (ref "X3") (pin "2") (pinfunction "2_2") (pintype "passive"))
    )
    (net (code "21") (name "Net-(DA1-IN+)") (class "Default")
      (node (ref "DA1") (pin "2") (pinfunction "IN+_2") (pintype "passive"))
      (node (ref "R3") (pin "2") (pinfunction "2_2") (pintype "passive"))
      (node (ref "X1") (pin "2") (pinfunction "2_2") (pintype "passive"))
    )
    (net (code "22") (name "Net-(DA1-IN-)") (class "Default")
      (node (ref "DA1") (pin "3") (pinfunction "IN-_3") (pintype "passive"))
      (node (ref "DA2") (pin "3") (pinfunction "IN-_3") (pintype "passive"))
      (node (ref "R1") (pin "2") (pinfunction "2_2") (pintype "passive"))
      (node (ref "X1") (pin "4") (pinfunction "4_4") (pintype "passive"))
    )
    (net (code "23") (name "Net-(DA1-OUT+)") (class "Default")
      (node (ref "DA1") (pin "6") (pinfunction "OUT+_6") (pintype "passive"))
      (node (ref "R9") (pin "1") (pinfunction "1_1") (pintype "passive"))
    )
    (net (code "24") (name "Net-(DA1-OUT-)") (class "Default")
      (node (ref "DA1") (pin "7") (pinfunction "OUT-_7") (pintype "passive"))
      (node (ref "R10") (pin "1") (pinfunction "1_1") (pintype "passive"))
    )
    (net (code "25") (name "Net-(DA2-IN+)") (class "Default")
      (node (ref "DA2") (pin "2") (pinfunction "IN+_2") (pintype "passive"))
      (node (ref "R4") (pin "2") (pinfunction "2_2") (pintype "passive"))
      (node (ref "X1") (pin "3") (pinfunction "3_3") (pintype "passive"))
    )
    (net (code "26") (name "Net-(DA2-OUT+)") (class "Default")
      (node (ref "DA2") (pin "6") (pinfunction "OUT+_6") (pintype "passive"))
      (node (ref "R11") (pin "1") (pinfunction "1_1") (pintype "passive"))
    )
    (net (code "27") (name "Net-(DA2-OUT-)") (class "Default")
      (node (ref "DA2") (pin "7") (pinfunction "OUT-_7") (pintype "passive"))
      (node (ref "R12") (pin "1") (pinfunction "1_1") (pintype "passive"))
    )
    (net (code "28") (name "Net-(DA3-IN+)") (class "Default")
      (node (ref "DA3") (pin "2") (pinfunction "IN+_2") (pintype "passive"))
      (node (ref "R5") (pin "2") (pinfunction "2_2") (pintype "passive"))
      (node (ref "X2") (pin "2") (pinfunction "2_2") (pintype "passive"))
    )
    (net (code "29") (name "Net-(DA3-IN-)") (class "Default")
      (node (ref "DA3") (pin "3") (pinfunction "IN-_3") (pintype "passive"))
      (node (ref "DA4") (pin "3") (pinfunction "IN-_3") (pintype "passive"))
      (node (ref "R2") (pin "2") (pinfunction "2_2") (pintype "passive"))
      (node (ref "X2") (pin "4") (pinfunction "4_4") (pintype "passive"))
    )
    (net (code "30") (name "Net-(DA3-OUT+)") (class "Default")
      (node (ref "DA3") (pin "6") (pinfunction "OUT+_6") (pintype "passive"))
      (node (ref "R13") (pin "1") (pinfunction "1_1") (pintype "passive"))
    )
    (net (code "31") (name "Net-(DA3-OUT-)") (class "Default")
      (node (ref "DA3") (pin "7") (pinfunction "OUT-_7") (pintype "passive"))
      (node (ref "R14") (pin "1") (pinfunction "1_1") (pintype "passive"))
    )
    (net (code "32") (name "Net-(DA4-IN+)") (class "Default")
      (node (ref "DA4") (pin "2") (pinfunction "IN+_2") (pintype "passive"))
      (node (ref "R6") (pin "2") (pinfunction "2_2") (pintype "passive"))
      (node (ref "X2") (pin "3") (pinfunction "3_3") (pintype "passive"))
    )
    (net (code "33") (name "Net-(DA4-OUT+)") (class "Default")
      (node (ref "DA4") (pin "6") (pinfunction "OUT+_6") (pintype "passive"))
      (node (ref "R15") (pin "1") (pinfunction "1_1") (pintype "passive"))
    )
    (net (code "34") (name "Net-(DA4-OUT-)") (class "Default")
      (node (ref "DA4") (pin "7") (pinfunction "OUT-_7") (pintype "passive"))
      (node (ref "R16") (pin "1") (pinfunction "1_1") (pintype "passive"))
    )
    (net (code "35") (name "Net-(DA5-+IN)") (class "Default")
      (node (ref "C17") (pin "1") (pinfunction "1_1") (pintype "passive"))
      (node (ref "DA5") (pin "1") (pinfunction "+IN_1") (pintype "passive"))
      (node (ref "R17") (pin "2") (pinfunction "2_2") (pintype "passive"))
      (node (ref "R23") (pin "1") (pinfunction "1_1") (pintype "passive"))
    )
    (net (code "36") (name "Net-(DA5--IN)") (class "Default")
      (node (ref "C16") (pin "2") (pinfunction "2_2") (pintype "passive"))
      (node (ref "DA5") (pin "3") (pinfunction "-IN_3") (pintype "passive"))
      (node (ref "R22") (pin "1") (pinfunction "1_1") (pintype "passive"))
      (node (ref "R8") (pin "2") (pinfunction "2_2") (pintype "passive"))
    )
    (net (code "37") (name "Net-(DA5-OUT)") (class "Default")
      (node (ref "C16") (pin "1") (pinfunction "1_1") (pintype "passive"))
      (node (ref "DA5") (pin "4") (pinfunction "OUT_4") (pintype "passive"))
      (node (ref "R7") (pin "2") (pinfunction "2_2") (pintype "passive"))
      (node (ref "R8") (pin "1") (pinfunction "1_1") (pintype "passive"))
    )
    (net (code "38") (name "Net-(R25-5)") (class "Default")
      (node (ref "C34") (pin "2") (pinfunction "2_2") (pintype "passive"))
      (node (ref "R23") (pin "2") (pinfunction "2_2") (pintype "passive"))
      (node (ref "R24") (pin "1") (pinfunction "1_1") (pintype "passive"))
      (node (ref "R25") (pin "2") (pinfunction "5_2") (pintype "passive"))
    )
    (net (code "39") (name "Net-(VT1-G)") (class "Default")
      (node (ref "R10") (pin "2") (pinfunction "2_2") (pintype "passive"))
      (node (ref "R18") (pin "2") (pinfunction "2_2") (pintype "passive"))
      (node (ref "R9") (pin "2") (pinfunction "2_2") (pintype "passive"))
      (node (ref "VT1") (pin "1") (pinfunction "G_1") (pintype "passive"))
    )
    (net (code "40") (name "Net-(VT2-G)") (class "Default")
      (node (ref "R11") (pin "2") (pinfunction "2_2") (pintype "passive"))
      (node (ref "R12") (pin "2") (pinfunction "2_2") (pintype "passive"))
      (node (ref "R19") (pin "2") (pinfunction "2_2") (pintype "passive"))
      (node (ref "VT2") (pin "1") (pinfunction "G_1") (pintype "passive"))
    )
    (net (code "41") (name "Net-(VT3-G)") (class "Default")
      (node (ref "R13") (pin "2") (pinfunction "2_2") (pintype "passive"))
      (node (ref "R14") (pin "2") (pinfunction "2_2") (pintype "passive"))
      (node (ref "R20") (pin "2") (pinfunction "2_2") (pintype "passive"))
      (node (ref "VT3") (pin "1") (pinfunction "G_1") (pintype "passive"))
    )
    (net (code "42") (name "Net-(VT4-G)") (class "Default")
      (node (ref "R15") (pin "2") (pinfunction "2_2") (pintype "passive"))
      (node (ref "R16") (pin "2") (pinfunction "2_2") (pintype "passive"))
      (node (ref "R21") (pin "2") (pinfunction "2_2") (pintype "passive"))
      (node (ref "VT4") (pin "1") (pinfunction "G_1") (pintype "passive"))
    )
    (net (code "43") (name "PGND") (class "Default")
      (node (ref "C1") (pin "2") (pinfunction "2_2") (pintype "passive"))
      (node (ref "C13") (pin "2") (pinfunction "2_2") (pintype "passive"))
      (node (ref "C15") (pin "2") (pinfunction "2_2") (pintype "passive"))
      (node (ref "C2") (pin "2") (pinfunction "2_2") (pintype "passive"))
      (node (ref "C20") (pin "1") (pinfunction "1_1") (pintype "passive"))
      (node (ref "C21") (pin "2") (pinfunction "2_2") (pintype "passive"))
      (node (ref "C24") (pin "1") (pinfunction "1_1") (pintype "passive"))
      (node (ref "C25") (pin "2") (pinfunction "2_2") (pintype "passive"))
      (node (ref "C26") (pin "2") (pinfunction "2_2") (pintype "passive"))
      (node (ref "C27") (pin "2") (pinfunction "2_2") (pintype "passive"))
      (node (ref "C28") (pin "2") (pinfunction "2_2") (pintype "passive"))
      (node (ref "C29") (pin "2") (pinfunction "2_2") (pintype "passive"))
      (node (ref "C30") (pin "1") (pinfunction "1_1") (pintype "passive"))
      (node (ref "C31") (pin "1") (pinfunction "1_1") (pintype "passive"))
      (node (ref "C32") (pin "1") (pinfunction "1_1") (pintype "passive"))
      (node (ref "C33") (pin "1") (pinfunction "1_1") (pintype "passive"))
      (node (ref "C34") (pin "1") (pinfunction "1_1") (pintype "passive"))
      (node (ref "DD2") (pin "6") (pinfunction "0V_6") (pintype "passive"))
      (node (ref "DD4") (pin "6") (pinfunction "0V_6") (pintype "passive"))
      (node (ref "R19") (pin "1") (pinfunction "1_1") (pintype "passive"))
      (node (ref "R21") (pin "1") (pinfunction "1_1") (pintype "passive"))
      (node (ref "R22") (pin "2") (pinfunction "2_2") (pintype "passive"))
      (node (ref "R25") (pin "1") (pinfunction "1_1") (pintype "passive"))
      (node (ref "VT2") (pin "3") (pinfunction "S_3") (pintype "passive"))
      (node (ref "VT4") (pin "3") (pinfunction "S_3") (pintype "passive"))
      (node (ref "X4") (pin "3") (pinfunction "3_3") (pintype "passive"))
      (node (ref "X4") (pin "4") (pinfunction "4_4") (pintype "passive"))
      (node (ref "X5") (pin "3") (pinfunction "3_3") (pintype "passive"))
      (node (ref "X5") (pin "4") (pinfunction "4_4") (pintype "passive"))
      (node (ref "X6") (pin "4") (pinfunction "4_4") (pintype "passive"))
      (node (ref "X6") (pin "5") (pinfunction "5_5") (pintype "passive"))
      (node (ref "X6") (pin "6") (pinfunction "6_6") (pintype "passive"))
      (node (ref "X7") (pin "4") (pinfunction "4_4") (pintype "passive"))
      (node (ref "X7") (pin "5") (pinfunction "5_5") (pintype "passive"))
      (node (ref "X7") (pin "6") (pinfunction "6_6") (pintype "passive"))
      (node (ref "X8") (pin "3") (pinfunction "3_3") (pintype "passive"))
      (node (ref "X8") (pin "4") (pinfunction "4_4") (pintype "passive"))
    )
  )
)
